# led-pb-wing.net
KiCad netlist of a schematic drawn in Altium Designer
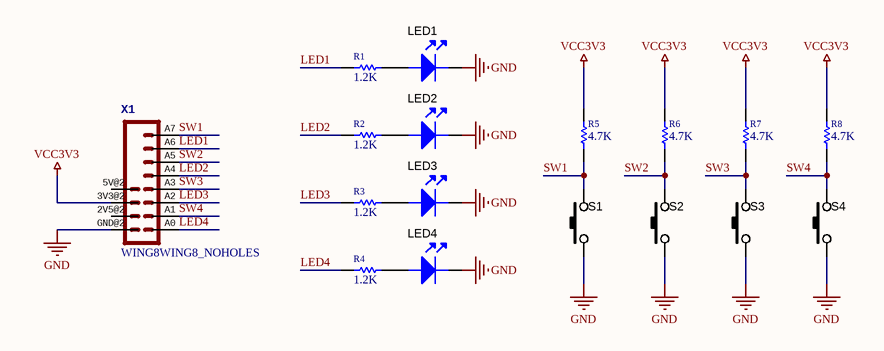
[diagram p0: led-pb-wing.SchDoc]

(export (version "E")
  (design (tool "Eeschema 10.0.6"))
  (components
    (comp (ref "LED1")
      (value "~")
      (footprint "LED_0805")
      (description "LED, 0805 SMD")
      (libsource (lib "MH - RCLDSX") (part "LED_0805"))
    )
    (comp (ref "LED2")
      (value "~")
      (footprint "LED_0805")
      (description "LED, 0805 SMD")
      (libsource (lib "MH - RCLDSX") (part "LED_0805"))
    )
    (comp (ref "LED3")
      (value "~")
      (footprint "LED_0805")
      (description "LED, 0805 SMD")
      (libsource (lib "MH - RCLDSX") (part "LED_0805"))
    )
    (comp (ref "LED4")
      (value "~")
      (footprint "LED_0805")
      (description "LED, 0805 SMD")
      (libsource (lib "MH - RCLDSX") (part "LED_0805"))
    )
    (comp (ref "R1")
      (value "1.2K")
      (footprint "R0805_M")
      (description "Chip Resistor size 0805")
      (libsource (lib "MH - RCLDSX") (part "R0805"))
    )
    (comp (ref "R2")
      (value "1.2K")
      (footprint "R0805_M")
      (description "Chip Resistor size 0805")
      (libsource (lib "MH - RCLDSX") (part "R0805"))
    )
    (comp (ref "R3")
      (value "1.2K")
      (footprint "R0805_M")
      (description "Chip Resistor size 0805")
      (libsource (lib "MH - RCLDSX") (part "R0805"))
    )
    (comp (ref "R4")
      (value "1.2K")
      (footprint "R0805_M")
      (description "Chip Resistor size 0805")
      (libsource (lib "MH - RCLDSX") (part "R0805"))
    )
    (comp (ref "R5")
      (value "4.7K")
      (footprint "R0805_M")
      (description "Chip Resistor size 0805")
      (libsource (lib "MH - RCLDSX") (part "R0805"))
    )
    (comp (ref "R6")
      (value "4.7K")
      (footprint "R0805_M")
      (description "Chip Resistor size 0805")
      (libsource (lib "MH - RCLDSX") (part "R0805"))
    )
    (comp (ref "R7")
      (value "4.7K")
      (footprint "R0805_M")
      (description "Chip Resistor size 0805")
      (libsource (lib "MH - RCLDSX") (part "R0805"))
    )
    (comp (ref "R8")
      (value "4.7K")
      (footprint "R0805_M")
      (description "Chip Resistor size 0805")
      (libsource (lib "MH - RCLDSX") (part "R0805"))
    )
    (comp (ref "S1")
      (value "USER PB")
      (footprint "TS645S")
      (description "SMT Tactile Switch (6mm x 6mm)")
      (libsource (lib "MH - RCLDSX") (part "SW_SMD_4Pin"))
    )
    (comp (ref "S2")
      (value "USER PB")
      (footprint "TS645S")
      (description "SMT Tactile Switch (6mm x 6mm)")
      (libsource (lib "MH - RCLDSX") (part "SW_SMD_4Pin"))
    )
    (comp (ref "S3")
      (value "USER PB")
      (footprint "TS645S")
      (description "SMT Tactile Switch (6mm x 6mm)")
      (libsource (lib "MH - RCLDSX") (part "SW_SMD_4Pin"))
    )
    (comp (ref "S4")
      (value "USER PB")
      (footprint "TS645S")
      (description "SMT Tactile Switch (6mm x 6mm)")
      (libsource (lib "MH - RCLDSX") (part "SW_SMD_4Pin"))
    )
    (comp (ref "X1")
      (value "WING8WING8_NOHOLES")
      (footprint "WINGSIDE_8BIT_NOHOLES")
      (libsource (lib "Papilio") (part "WING8WING8_NOHOLES"))
    )
  )
  (nets
    (net (code "1") (name "/LED1") (class "Default")
      (node (ref "R1") (pin "2") (pinfunction "2_2") (pintype "passive"))
      (node (ref "X1") (pin "A6") (pinfunction "A6_A6") (pintype "passive"))
    )
    (net (code "2") (name "/LED2") (class "Default")
      (node (ref "R2") (pin "2") (pinfunction "2_2") (pintype "passive"))
      (node (ref "X1") (pin "A4") (pinfunction "A4_A4") (pintype "passive"))
    )
    (net (code "3") (name "/LED3") (class "Default")
      (node (ref "R3") (pin "2") (pinfunction "2_2") (pintype "passive"))
      (node (ref "X1") (pin "A2") (pinfunction "A2_A2") (pintype "passive"))
    )
    (net (code "4") (name "/LED4") (class "Default")
      (node (ref "R4") (pin "2") (pinfunction "2_2") (pintype "passive"))
      (node (ref "X1") (pin "A0") (pinfunction "A0_A0") (pintype "passive"))
    )
    (net (code "5") (name "/SW1") (class "Default")
      (node (ref "R5") (pin "1") (pinfunction "1_1") (pintype "passive"))
      (node (ref "S1") (pin "2") (pintype "passive"))
      (node (ref "X1") (pin "A7") (pinfunction "A7_A7") (pintype "passive"))
    )
    (net (code "6") (name "/SW2") (class "Default")
      (node (ref "R6") (pin "1") (pinfunction "1_1") (pintype "passive"))
      (node (ref "S2") (pin "2") (pintype "passive"))
      (node (ref "X1") (pin "A5") (pinfunction "A5_A5") (pintype "passive"))
    )
    (net (code "7") (name "/SW3") (class "Default")
      (node (ref "R7") (pin "1") (pinfunction "1_1") (pintype "passive"))
      (node (ref "S3") (pin "2") (pintype "passive"))
      (node (ref "X1") (pin "A3") (pinfunction "A3_A3") (pintype "passive"))
    )
    (net (code "8") (name "/SW4") (class "Default")
      (node (ref "R8") (pin "1") (pinfunction "1_1") (pintype "passive"))
      (node (ref "S4") (pin "2") (pintype "passive"))
      (node (ref "X1") (pin "A1") (pinfunction "A1_A1") (pintype "passive"))
    )
    (net (code "9") (name "GND") (class "Default")
      (node (ref "LED1") (pin "1") (pinfunction "cathode_1") (pintype "passive"))
      (node (ref "LED2") (pin "1") (pinfunction "cathode_1") (pintype "passive"))
      (node (ref "LED3") (pin "1") (pinfunction "cathode_1") (pintype "passive"))
      (node (ref "LED4") (pin "1") (pinfunction "cathode_1") (pintype "passive"))
      (node (ref "S1") (pin "1") (pintype "passive"))
      (node (ref "S2") (pin "1") (pintype "passive"))
      (node (ref "S3") (pin "1") (pintype "passive"))
      (node (ref "S4") (pin "1") (pintype "passive"))
      (node (ref "X1") (pin "GND@2") (pinfunction "GND_GND@2") (pintype "passive"))
    )
    (net (code "10") (name "Net-(LED1-ANODE)") (class "Default")
      (node (ref "LED1") (pin "2") (pinfunction "ANODE_2") (pintype "passive"))
      (node (ref "R1") (pin "1") (pinfunction "1_1") (pintype "passive"))
    )
    (net (code "11") (name "Net-(LED2-ANODE)") (class "Default")
      (node (ref "LED2") (pin "2") (pinfunction "ANODE_2") (pintype "passive"))
      (node (ref "R2") (pin "1") (pinfunction "1_1") (pintype "passive"))
    )
    (net (code "12") (name "Net-(LED3-ANODE)") (class "Default")
      (node (ref "LED3") (pin "2") (pinfunction "ANODE_2") (pintype "passive"))
      (node (ref "R3") (pin "1") (pinfunction "1_1") (pintype "passive"))
    )
    (net (code "13") (name "Net-(LED4-ANODE)") (class "Default")
      (node (ref "LED4") (pin "2") (pinfunction "ANODE_2") (pintype "passive"))
      (node (ref "R4") (pin "1") (pinfunction "1_1") (pintype "passive"))
    )
    (net (code "14") (name "VCC3V3") (class "Default")
      (node (ref "R5") (pin "2") (pinfunction "2_2") (pintype "passive"))
      (node (ref "R6") (pin "2") (pinfunction "2_2") (pintype "passive"))
      (node (ref "R7") (pin "2") (pinfunction "2_2") (pintype "passive"))
      (node (ref "R8") (pin "2") (pinfunction "2_2") (pintype "passive"))
      (node (ref "X1") (pin "3V3@2") (pinfunction "3V3_3V3@2") (pintype "passive"))
    )
    (net (code "15") (name "unconnected-(X1-2V5-Pad2V5@2)") (class "Default")
      (node (ref "X1") (pin "2V5@2") (pinfunction "2V5_2V5@2") (pintype "passive"))
    )
    (net (code "16") (name "unconnected-(X1-5V-Pad5V@2)") (class "Default")
      (node (ref "X1") (pin "5V@2") (pinfunction "5V_5V@2") (pintype "passive"))
    )
  )
)
